# MotorControl.net
KiCad netlist of a schematic drawn in EAGLE
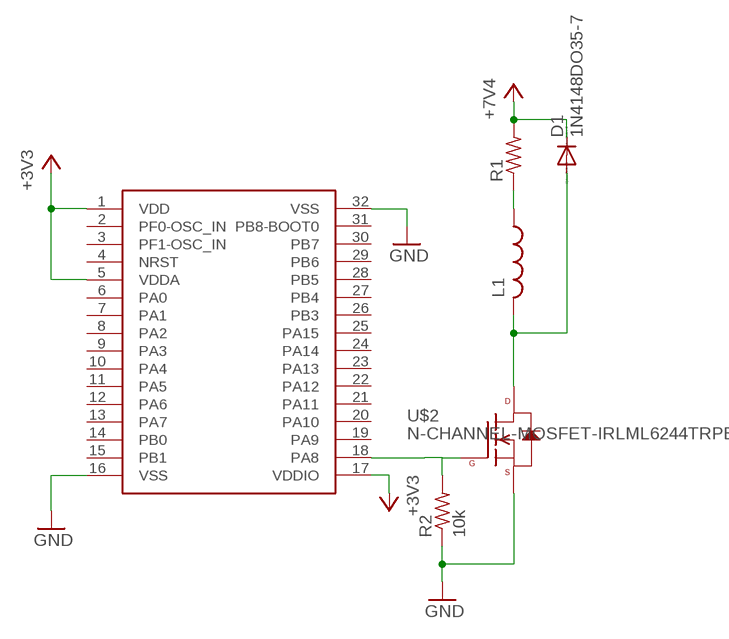
[diagram p0: schematic, sheet 1]

(export (version "E")
  (design (tool "Eeschema 10.0.6"))
  (components
    (comp (ref "D1")
      (value "1N4148DO35-7")
      (footprint "eagle-import:DO35-7")
      (libsource (lib "eagle-import") (part "1N4148DO35-7"))
    )
    (comp (ref "L1")
      (value "L-US0204/7")
      (footprint "eagle-import:0204_7")
      (libsource (lib "eagle-import") (part "L-US0204/7"))
    )
    (comp (ref "R1")
      (value "R-US_0207/2V")
      (footprint "eagle-import:0207_2V")
      (libsource (lib "eagle-import") (part "R-US_0207/2V"))
    )
    (comp (ref "R2")
      (value "10k")
      (footprint "eagle-import:0207_2V")
      (libsource (lib "eagle-import") (part "R-US_0207/2V"))
    )
    (comp (ref "U$1")
      (value "STM32F042K6LQFP32")
      (footprint "eagle-import:QFP80P900X900X120-32")
      (libsource (lib "eagle-import") (part "STM32F042K6LQFP32"))
    )
    (comp (ref "U$2")
      (value "N-CHANNEL-MOSFET-IRLML6244TRPBF")
      (footprint "eagle-import:SOT23-3")
      (libsource (lib "eagle-import") (part "N-CHANNEL-MOSFET-IRLML6244TRPBF"))
    )
  )
  (nets
    (net (code "1") (name "+3V3") (class "Default")
      (node (ref "U$1") (pin "1") (pinfunction "VDD_1") (pintype "bidirectional"))
      (node (ref "U$1") (pin "17") (pinfunction "VDDIO_17") (pintype "bidirectional"))
      (node (ref "U$1") (pin "5") (pinfunction "VDDA_5") (pintype "bidirectional"))
    )
    (net (code "2") (name "+7V4") (class "Default")
      (node (ref "D1") (pin "C") (pinfunction "C_C") (pintype "passive"))
      (node (ref "R1") (pin "2") (pinfunction "2_2") (pintype "passive"))
    )
    (net (code "3") (name "GND") (class "Default")
      (node (ref "R2") (pin "1") (pinfunction "1_1") (pintype "passive"))
      (node (ref "U$1") (pin "16") (pinfunction "VSS_16") (pintype "bidirectional"))
      (node (ref "U$1") (pin "32") (pinfunction "VSS_32") (pintype "bidirectional"))
      (node (ref "U$2") (pin "2") (pinfunction "S_2") (pintype "passive"))
    )
    (net (code "4") (name "Net-(L1-Pad1)") (class "Default")
      (node (ref "L1") (pin "1") (pinfunction "1_1") (pintype "passive"))
      (node (ref "R1") (pin "1") (pinfunction "1_1") (pintype "passive"))
    )
    (net (code "5") (name "Net-(U$1-PA8)") (class "Default")
      (node (ref "R2") (pin "2") (pinfunction "2_2") (pintype "passive"))
      (node (ref "U$1") (pin "18") (pinfunction "PA8_18") (pintype "bidirectional"))
      (node (ref "U$2") (pin "1") (pinfunction "G_1") (pintype "passive"))
    )
    (net (code "6") (name "Net-(U$2-D)") (class "Default")
      (node (ref "D1") (pin "A") (pinfunction "A_A") (pintype "passive"))
      (node (ref "L1") (pin "2") (pinfunction "2_2") (pintype "passive"))
      (node (ref "U$2") (pin "3") (pinfunction "D_3") (pintype "passive"))
    )
    (net (code "7") (name "unconnected-(U$1-NRST-Pad4)") (class "Default")
      (node (ref "U$1") (pin "4") (pinfunction "NRST_4") (pintype "bidirectional"))
    )
    (net (code "8") (name "unconnected-(U$1-PA0-Pad6)") (class "Default")
      (node (ref "U$1") (pin "6") (pinfunction "PA0_6") (pintype "bidirectional"))
    )
    (net (code "9") (name "unconnected-(U$1-PA1-Pad7)") (class "Default")
      (node (ref "U$1") (pin "7") (pinfunction "PA1_7") (pintype "bidirectional"))
    )
    (net (code "10") (name "unconnected-(U$1-PA2-Pad8)") (class "Default")
      (node (ref "U$1") (pin "8") (pinfunction "PA2_8") (pintype "bidirectional"))
    )
    (net (code "11") (name "unconnected-(U$1-PA3-Pad9)") (class "Default")
      (node (ref "U$1") (pin "9") (pinfunction "PA3_9") (pintype "bidirectional"))
    )
    (net (code "12") (name "unconnected-(U$1-PA4-Pad10)") (class "Default")
      (node (ref "U$1") (pin "10") (pinfunction "PA4_10") (pintype "bidirectional"))
    )
    (net (code "13") (name "unconnected-(U$1-PA5-Pad11)") (class "Default")
      (node (ref "U$1") (pin "11") (pinfunction "PA5_11") (pintype "bidirectional"))
    )
    (net (code "14") (name "unconnected-(U$1-PA6-Pad12)") (class "Default")
      (node (ref "U$1") (pin "12") (pinfunction "PA6_12") (pintype "bidirectional"))
    )
    (net (code "15") (name "unconnected-(U$1-PA7-Pad13)") (class "Default")
      (node (ref "U$1") (pin "13") (pinfunction "PA7_13") (pintype "bidirectional"))
    )
    (net (code "16") (name "unconnected-(U$1-PA9-Pad19)") (class "Default")
      (node (ref "U$1") (pin "19") (pinfunction "PA9_19") (pintype "bidirectional"))
    )
    (net (code "17") (name "unconnected-(U$1-PA10-Pad20)") (class "Default")
      (node (ref "U$1") (pin "20") (pinfunction "PA10_20") (pintype "bidirectional"))
    )
    (net (code "18") (name "unconnected-(U$1-PA11-Pad21)") (class "Default")
      (node (ref "U$1") (pin "21") (pinfunction "PA11_21") (pintype "bidirectional"))
    )
    (net (code "19") (name "unconnected-(U$1-PA12-Pad22)") (class "Default")
      (node (ref "U$1") (pin "22") (pinfunction "PA12_22") (pintype "bidirectional"))
    )
    (net (code "20") (name "unconnected-(U$1-PA13-Pad23)") (class "Default")
      (node (ref "U$1") (pin "23") (pinfunction "PA13_23") (pintype "bidirectional"))
    )
    (net (code "21") (name "unconnected-(U$1-PA14-Pad24)") (class "Default")
      (node (ref "U$1") (pin "24") (pinfunction "PA14_24") (pintype "bidirectional"))
    )
    (net (code "22") (name "unconnected-(U$1-PA15-Pad25)") (class "Default")
      (node (ref "U$1") (pin "25") (pinfunction "PA15_25") (pintype "bidirectional"))
    )
    (net (code "23") (name "unconnected-(U$1-PB0-Pad14)") (class "Default")
      (node (ref "U$1") (pin "14") (pinfunction "PB0_14") (pintype "bidirectional"))
    )
    (net (code "24") (name "unconnected-(U$1-PB1-Pad15)") (class "Default")
      (node (ref "U$1") (pin "15") (pinfunction "PB1_15") (pintype "bidirectional"))
    )
    (net (code "25") (name "unconnected-(U$1-PB3-Pad26)") (class "Default")
      (node (ref "U$1") (pin "26") (pinfunction "PB3_26") (pintype "bidirectional"))
    )
    (net (code "26") (name "unconnected-(U$1-PB4-Pad27)") (class "Default")
      (node (ref "U$1") (pin "27") (pinfunction "PB4_27") (pintype "bidirectional"))
    )
    (net (code "27") (name "unconnected-(U$1-PB5-Pad28)") (class "Default")
      (node (ref "U$1") (pin "28") (pinfunction "PB5_28") (pintype "bidirectional"))
    )
    (net (code "28") (name "unconnected-(U$1-PB6-Pad29)") (class "Default")
      (node (ref "U$1") (pin "29") (pinfunction "PB6_29") (pintype "bidirectional"))
    )
    (net (code "29") (name "unconnected-(U$1-PB7-Pad30)") (class "Default")
      (node (ref "U$1") (pin "30") (pinfunction "PB7_30") (pintype "bidirectional"))
    )
    (net (code "30") (name "unconnected-(U$1-PB8-BOOT0-Pad31)") (class "Default")
      (node (ref "U$1") (pin "31") (pinfunction "PB8-BOOT0_31") (pintype "bidirectional"))
    )
    (net (code "31") (name "unconnected-(U$1-PF0-OSC_IN-Pad2)") (class "Default")
      (node (ref "U$1") (pin "2") (pinfunction "PF0-OSC_IN_2") (pintype "bidirectional"))
    )
    (net (code "32") (name "unconnected-(U$1-PF1-OSC_IN-Pad3)") (class "Default")
      (node (ref "U$1") (pin "3") (pinfunction "PF1-OSC_IN_3") (pintype "bidirectional"))
    )
  )
)
